# RGB_Encoder_Switcher_QSB_v1p2.net
KiCad netlist of a schematic drawn in EAGLE
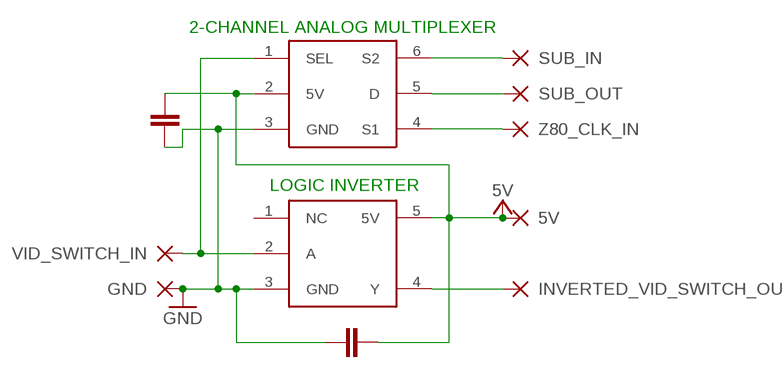
[diagram p0: schematic, sheet 1]

(export (version "E")
  (design (tool "Eeschema 10.0.6"))
  (components
    (comp (ref "5V")
      (value "PADSCIRCLE-1,5X1,5")
      (footprint "eagle-import:CIRCLE-1,5X1,5")
      (libsource (lib "eagle-import") (part "PADSCIRCLE-1,5X1,5"))
    )
    (comp (ref "C1")
      (value "0.1uF")
      (footprint "eagle-import:C0603")
      (libsource (lib "eagle-import") (part "CAPACITORSC0603"))
    )
    (comp (ref "C2")
      (value "0.1uF")
      (footprint "eagle-import:C0603")
      (libsource (lib "eagle-import") (part "CAPACITORSC0603"))
    )
    (comp (ref "GND")
      (value "PADSCIRCLE-1,5X1,5")
      (footprint "eagle-import:CIRCLE-1,5X1,5")
      (libsource (lib "eagle-import") (part "PADSCIRCLE-1,5X1,5"))
    )
    (comp (ref "INVERTED_VID_SWITCH_OUT")
      (value "PADSCIRCLE-1,5X1,5")
      (footprint "eagle-import:CIRCLE-1,5X1,5")
      (libsource (lib "eagle-import") (part "PADSCIRCLE-1,5X1,5"))
    )
    (comp (ref "INVERTER")
      (value "74AHCT1G04DBVRE4")
      (footprint "eagle-import:SOT95P280X110-5N")
      (libsource (lib "eagle-import") (part "74AHCT1G04DBVRE4"))
    )
    (comp (ref "MULTIPLEXER")
      (value "TMUX1219DBVR")
      (footprint "eagle-import:SOT95P280X110-6N")
      (libsource (lib "eagle-import") (part "TMUX1219DBVR"))
    )
    (comp (ref "SUB_IN")
      (value "PADSCIRCLE-1,5X1,5")
      (footprint "eagle-import:CIRCLE-1,5X1,5")
      (libsource (lib "eagle-import") (part "PADSCIRCLE-1,5X1,5"))
    )
    (comp (ref "SUB_OUT")
      (value "PADSCIRCLE-1,5X1,5")
      (footprint "eagle-import:CIRCLE-1,5X1,5")
      (libsource (lib "eagle-import") (part "PADSCIRCLE-1,5X1,5"))
    )
    (comp (ref "VID_SWITCH_IN")
      (value "PADSCIRCLE-1,5X1,5")
      (footprint "eagle-import:CIRCLE-1,5X1,5")
      (libsource (lib "eagle-import") (part "PADSCIRCLE-1,5X1,5"))
    )
    (comp (ref "Z80_CLK_IN")
      (value "PADSCIRCLE-1,5X1,5")
      (footprint "eagle-import:CIRCLE-1,5X1,5")
      (libsource (lib "eagle-import") (part "PADSCIRCLE-1,5X1,5"))
    )
  )
  (nets
    (net (code "1") (name "5V") (class "Default")
      (node (ref "5V") (pin "1") (pinfunction "P_1") (pintype "passive"))
      (node (ref "C1") (pin "1") (pinfunction "1_1") (pintype "passive"))
      (node (ref "C2") (pin "2") (pinfunction "2_2") (pintype "passive"))
      (node (ref "INVERTER") (pin "5") (pinfunction "5V_5") (pintype "bidirectional"))
      (node (ref "MULTIPLEXER") (pin "2") (pinfunction "5V_2") (pintype "power_in"))
    )
    (net (code "2") (name "GND") (class "Default")
      (node (ref "C1") (pin "2") (pinfunction "2_2") (pintype "passive"))
      (node (ref "C2") (pin "1") (pinfunction "1_1") (pintype "passive"))
      (node (ref "GND") (pin "1") (pinfunction "P_1") (pintype "passive"))
      (node (ref "INVERTER") (pin "3") (pinfunction "GND_3") (pintype "bidirectional"))
      (node (ref "MULTIPLEXER") (pin "3") (pinfunction "GND_3") (pintype "power_in"))
    )
    (net (code "3") (name "Net-(INVERTED_VID_SWITCH_OUT-P)") (class "Default")
      (node (ref "INVERTED_VID_SWITCH_OUT") (pin "1") (pinfunction "P_1") (pintype "passive"))
      (node (ref "INVERTER") (pin "4") (pinfunction "Y_4") (pintype "output"))
    )
    (net (code "4") (name "Net-(INVERTER-A)") (class "Default")
      (node (ref "INVERTER") (pin "2") (pinfunction "A_2") (pintype "input"))
      (node (ref "MULTIPLEXER") (pin "1") (pinfunction "SEL_1") (pintype "bidirectional"))
      (node (ref "VID_SWITCH_IN") (pin "1") (pinfunction "P_1") (pintype "passive"))
    )
    (net (code "5") (name "Net-(MULTIPLEXER-D)") (class "Default")
      (node (ref "MULTIPLEXER") (pin "5") (pinfunction "D_5") (pintype "bidirectional"))
      (node (ref "SUB_OUT") (pin "1") (pinfunction "P_1") (pintype "passive"))
    )
    (net (code "6") (name "Net-(MULTIPLEXER-S1)") (class "Default")
      (node (ref "MULTIPLEXER") (pin "4") (pinfunction "S1_4") (pintype "bidirectional"))
      (node (ref "Z80_CLK_IN") (pin "1") (pinfunction "P_1") (pintype "passive"))
    )
    (net (code "7") (name "Net-(MULTIPLEXER-S2)") (class "Default")
      (node (ref "MULTIPLEXER") (pin "6") (pinfunction "S2_6") (pintype "bidirectional"))
      (node (ref "SUB_IN") (pin "1") (pinfunction "P_1") (pintype "passive"))
    )
    (net (code "8") (name "unconnected-(INVERTER-NC-Pad1)") (class "Default")
      (node (ref "INVERTER") (pin "1") (pinfunction "NC_1") (pintype "no_connect"))
    )
  )
)
